# Power.net
KiCad netlist of a schematic drawn in Altium Designer
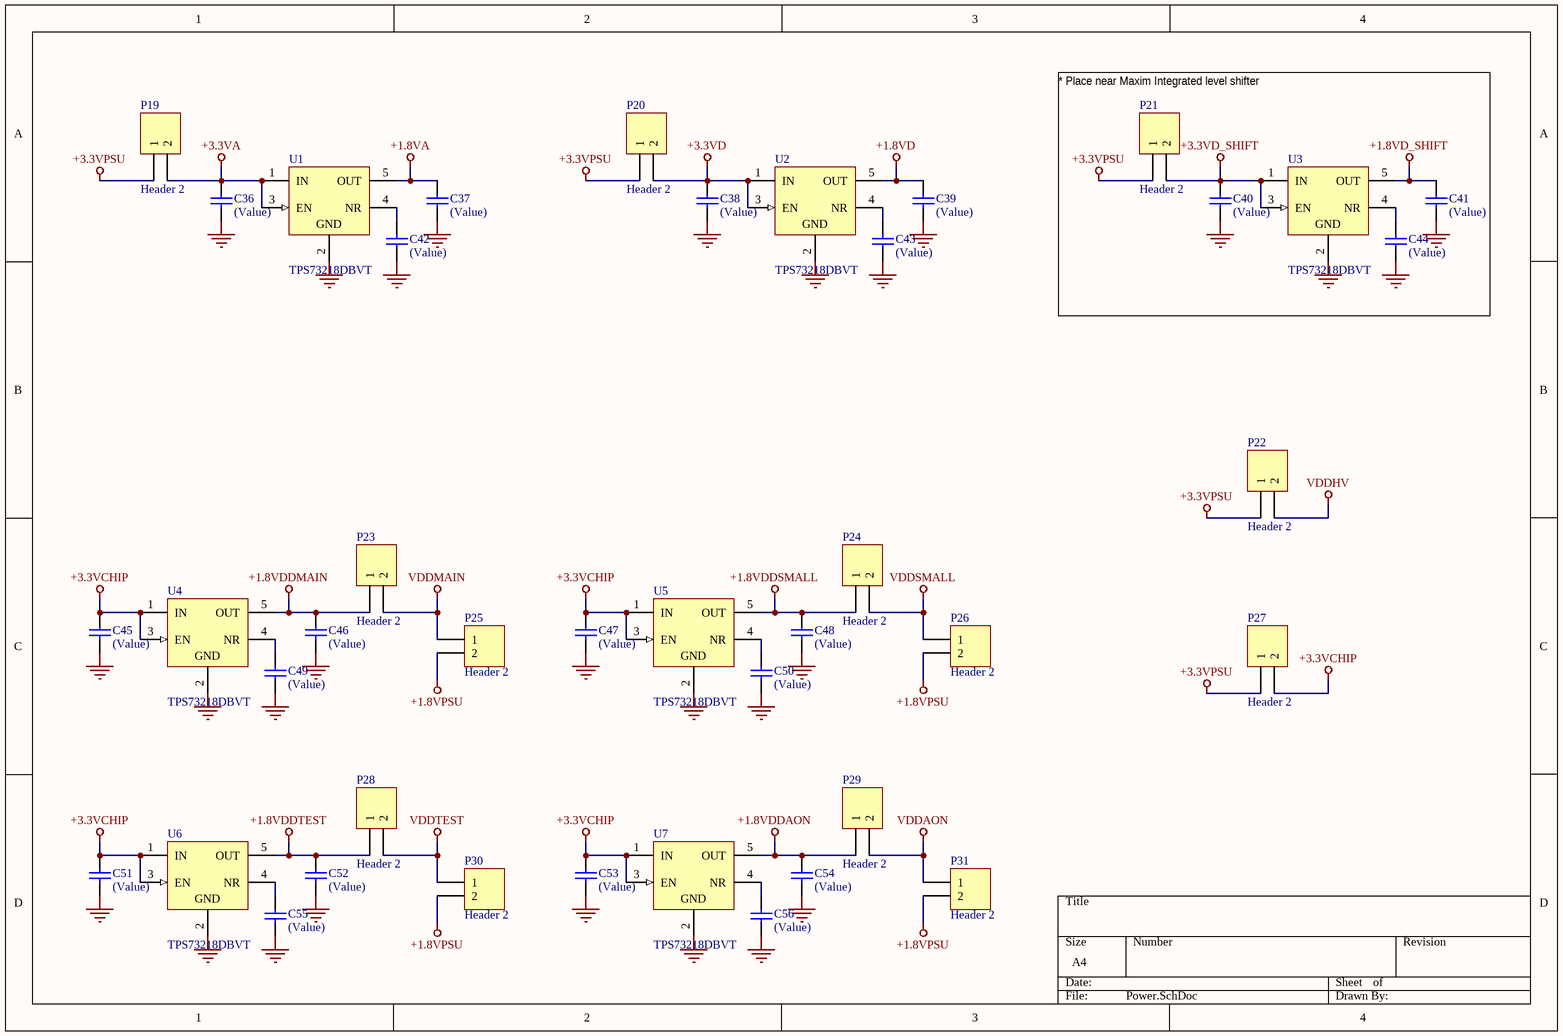
[diagram p0: Power.SchDoc]

(export (version "E")
  (design (tool "Eeschema 10.0.6"))
  (components
    (comp (ref "C36")
      (value "(Value)")
      (footprint "CAPC1608X90X35ML10T15")
      (description "0603")
      (fields (field (name "MANUFACTURER") "Murata"))
      (libsource (lib "Altium Content Vault") (part "CAP-NP-2"))
    )
    (comp (ref "C37")
      (value "(Value)")
      (footprint "CAPC1608X90X35ML10T15")
      (description "0603")
      (fields (field (name "MANUFACTURER") "Murata"))
      (libsource (lib "Altium Content Vault") (part "CAP-NP-2"))
    )
    (comp (ref "C38")
      (value "(Value)")
      (footprint "CAPC1608X90X35ML10T15")
      (description "0603")
      (fields (field (name "MANUFACTURER") "Murata"))
      (libsource (lib "Altium Content Vault") (part "CAP-NP-2"))
    )
    (comp (ref "C39")
      (value "(Value)")
      (footprint "CAPC1608X90X35ML10T15")
      (description "0603")
      (fields (field (name "MANUFACTURER") "Murata"))
      (libsource (lib "Altium Content Vault") (part "CAP-NP-2"))
    )
    (comp (ref "C40")
      (value "(Value)")
      (footprint "CAPC1608X90X35ML10T15")
      (description "0603")
      (fields (field (name "MANUFACTURER") "Murata"))
      (libsource (lib "Altium Content Vault") (part "CAP-NP-2"))
    )
    (comp (ref "C41")
      (value "(Value)")
      (footprint "CAPC1608X90X35ML10T15")
      (description "0603")
      (fields (field (name "MANUFACTURER") "Murata"))
      (libsource (lib "Altium Content Vault") (part "CAP-NP-2"))
    )
    (comp (ref "C42")
      (value "(Value)")
      (footprint "CAPC1608X90X35ML10T15")
      (description "0603")
      (fields (field (name "MANUFACTURER") "Murata"))
      (libsource (lib "Altium Content Vault") (part "CAP-NP-2"))
    )
    (comp (ref "C43")
      (value "(Value)")
      (footprint "CAPC1608X90X35ML10T15")
      (description "0603")
      (fields (field (name "MANUFACTURER") "Murata"))
      (libsource (lib "Altium Content Vault") (part "CAP-NP-2"))
    )
    (comp (ref "C44")
      (value "(Value)")
      (footprint "CAPC1608X90X35ML10T15")
      (description "0603")
      (fields (field (name "MANUFACTURER") "Murata"))
      (libsource (lib "Altium Content Vault") (part "CAP-NP-2"))
    )
    (comp (ref "C45")
      (value "(Value)")
      (footprint "CAPC1608X90X35ML10T15")
      (description "0603")
      (fields (field (name "MANUFACTURER") "Murata"))
      (libsource (lib "Altium Content Vault") (part "CAP-NP-2"))
    )
    (comp (ref "C46")
      (value "(Value)")
      (footprint "CAPC1608X90X35ML10T15")
      (description "0603")
      (fields (field (name "MANUFACTURER") "Murata"))
      (libsource (lib "Altium Content Vault") (part "CAP-NP-2"))
    )
    (comp (ref "C47")
      (value "(Value)")
      (footprint "CAPC1608X90X35ML10T15")
      (description "0603")
      (fields (field (name "MANUFACTURER") "Murata"))
      (libsource (lib "Altium Content Vault") (part "CAP-NP-2"))
    )
    (comp (ref "C48")
      (value "(Value)")
      (footprint "CAPC1608X90X35ML10T15")
      (description "0603")
      (fields (field (name "MANUFACTURER") "Murata"))
      (libsource (lib "Altium Content Vault") (part "CAP-NP-2"))
    )
    (comp (ref "C49")
      (value "(Value)")
      (footprint "CAPC1608X90X35ML10T15")
      (description "0603")
      (fields (field (name "MANUFACTURER") "Murata"))
      (libsource (lib "Altium Content Vault") (part "CAP-NP-2"))
    )
    (comp (ref "C50")
      (value "(Value)")
      (footprint "CAPC1608X90X35ML10T15")
      (description "0603")
      (fields (field (name "MANUFACTURER") "Murata"))
      (libsource (lib "Altium Content Vault") (part "CAP-NP-2"))
    )
    (comp (ref "C51")
      (value "(Value)")
      (footprint "CAPC1608X90X35ML10T15")
      (description "0603")
      (fields (field (name "MANUFACTURER") "Murata"))
      (libsource (lib "Altium Content Vault") (part "CAP-NP-2"))
    )
    (comp (ref "C52")
      (value "(Value)")
      (footprint "CAPC1608X90X35ML10T15")
      (description "0603")
      (fields (field (name "MANUFACTURER") "Murata"))
      (libsource (lib "Altium Content Vault") (part "CAP-NP-2"))
    )
    (comp (ref "C53")
      (value "(Value)")
      (footprint "CAPC1608X90X35ML10T15")
      (description "0603")
      (fields (field (name "MANUFACTURER") "Murata"))
      (libsource (lib "Altium Content Vault") (part "CAP-NP-2"))
    )
    (comp (ref "C54")
      (value "(Value)")
      (footprint "CAPC1608X90X35ML10T15")
      (description "0603")
      (fields (field (name "MANUFACTURER") "Murata"))
      (libsource (lib "Altium Content Vault") (part "CAP-NP-2"))
    )
    (comp (ref "C55")
      (value "(Value)")
      (footprint "CAPC1608X90X35ML10T15")
      (description "0603")
      (fields (field (name "MANUFACTURER") "Murata"))
      (libsource (lib "Altium Content Vault") (part "CAP-NP-2"))
    )
    (comp (ref "C56")
      (value "(Value)")
      (footprint "CAPC1608X90X35ML10T15")
      (description "0603")
      (fields (field (name "MANUFACTURER") "Murata"))
      (libsource (lib "Altium Content Vault") (part "CAP-NP-2"))
    )
    (comp (ref "P19")
      (value "Header 2")
      (footprint "HDR1X2")
      (description "Header, 2-Pin")
      (fields (field (name "PUBLISHER") "Altium Limited"))
      (libsource (lib "Miscellaneous Connectors") (part "Header 2"))
    )
    (comp (ref "P20")
      (value "Header 2")
      (footprint "HDR1X2")
      (description "Header, 2-Pin")
      (fields (field (name "PUBLISHER") "Altium Limited"))
      (libsource (lib "Miscellaneous Connectors") (part "Header 2"))
    )
    (comp (ref "P21")
      (value "Header 2")
      (footprint "HDR1X2")
      (description "Header, 2-Pin")
      (fields (field (name "PUBLISHER") "Altium Limited"))
      (libsource (lib "Miscellaneous Connectors") (part "Header 2"))
    )
    (comp (ref "P22")
      (value "Header 2")
      (footprint "HDR1X2")
      (description "Header, 2-Pin")
      (fields (field (name "PUBLISHER") "Altium Limited"))
      (libsource (lib "Miscellaneous Connectors") (part "Header 2"))
    )
    (comp (ref "P23")
      (value "Header 2")
      (footprint "HDR1X2")
      (description "Header, 2-Pin")
      (fields (field (name "PUBLISHER") "Altium Limited"))
      (libsource (lib "Miscellaneous Connectors") (part "Header 2"))
    )
    (comp (ref "P24")
      (value "Header 2")
      (footprint "HDR1X2")
      (description "Header, 2-Pin")
      (fields (field (name "PUBLISHER") "Altium Limited"))
      (libsource (lib "Miscellaneous Connectors") (part "Header 2"))
    )
    (comp (ref "P25")
      (value "Header 2")
      (footprint "HDR1X2")
      (description "Header, 2-Pin")
      (fields (field (name "PUBLISHER") "Altium Limited"))
      (libsource (lib "") (part "Header 2_1"))
    )
    (comp (ref "P26")
      (value "Header 2")
      (footprint "HDR1X2")
      (description "Header, 2-Pin")
      (fields (field (name "PUBLISHER") "Altium Limited"))
      (libsource (lib "") (part "Header 2_1"))
    )
    (comp (ref "P27")
      (value "Header 2")
      (footprint "HDR1X2")
      (description "Header, 2-Pin")
      (fields (field (name "PUBLISHER") "Altium Limited"))
      (libsource (lib "Miscellaneous Connectors") (part "Header 2"))
    )
    (comp (ref "P28")
      (value "Header 2")
      (footprint "HDR1X2")
      (description "Header, 2-Pin")
      (fields (field (name "PUBLISHER") "Altium Limited"))
      (libsource (lib "Miscellaneous Connectors") (part "Header 2"))
    )
    (comp (ref "P29")
      (value "Header 2")
      (footprint "HDR1X2")
      (description "Header, 2-Pin")
      (fields (field (name "PUBLISHER") "Altium Limited"))
      (libsource (lib "Miscellaneous Connectors") (part "Header 2"))
    )
    (comp (ref "P30")
      (value "Header 2")
      (footprint "HDR1X2")
      (description "Header, 2-Pin")
      (fields (field (name "PUBLISHER") "Altium Limited"))
      (libsource (lib "") (part "Header 2_1"))
    )
    (comp (ref "P31")
      (value "Header 2")
      (footprint "HDR1X2")
      (description "Header, 2-Pin")
      (fields (field (name "PUBLISHER") "Altium Limited"))
      (libsource (lib "") (part "Header 2_1"))
    )
    (comp (ref "U1")
      (value "TPS73218DBVT")
      (footprint "DBV0005A_N")
      (fields (field (name "MANUFACTURER") "Texas Instruments"))
      (libsource (lib "Altium Content Vault") (part "TI-TPS79NXX-YYSOT5"))
    )
    (comp (ref "U2")
      (value "TPS73218DBVT")
      (footprint "DBV0005A_N")
      (fields (field (name "MANUFACTURER") "Texas Instruments"))
      (libsource (lib "Altium Content Vault") (part "TI-TPS79NXX-YYSOT5"))
    )
    (comp (ref "U3")
      (value "TPS73218DBVT")
      (footprint "DBV0005A_N")
      (fields (field (name "MANUFACTURER") "Texas Instruments"))
      (libsource (lib "Altium Content Vault") (part "TI-TPS79NXX-YYSOT5"))
    )
    (comp (ref "U4")
      (value "TPS73218DBVT")
      (footprint "DBV0005A_N")
      (fields (field (name "MANUFACTURER") "Texas Instruments"))
      (libsource (lib "Altium Content Vault") (part "TI-TPS79NXX-YYSOT5"))
    )
    (comp (ref "U5")
      (value "TPS73218DBVT")
      (footprint "DBV0005A_N")
      (fields (field (name "MANUFACTURER") "Texas Instruments"))
      (libsource (lib "Altium Content Vault") (part "TI-TPS79NXX-YYSOT5"))
    )
    (comp (ref "U6")
      (value "TPS73218DBVT")
      (footprint "DBV0005A_N")
      (fields (field (name "MANUFACTURER") "Texas Instruments"))
      (libsource (lib "Altium Content Vault") (part "TI-TPS79NXX-YYSOT5"))
    )
    (comp (ref "U7")
      (value "TPS73218DBVT")
      (footprint "DBV0005A_N")
      (fields (field (name "MANUFACTURER") "Texas Instruments"))
      (libsource (lib "Altium Content Vault") (part "TI-TPS79NXX-YYSOT5"))
    )
  )
  (nets
    (net (code "1") (name "+1.8VA") (class "Default")
      (node (ref "C37") (pin "1") (pinfunction "1_1") (pintype "passive"))
      (node (ref "U1") (pin "5") (pinfunction "OUT_5") (pintype "power_in"))
    )
    (net (code "2") (name "+1.8VD") (class "Default")
      (node (ref "C39") (pin "1") (pinfunction "1_1") (pintype "passive"))
      (node (ref "U2") (pin "5") (pinfunction "OUT_5") (pintype "power_in"))
    )
    (net (code "3") (name "+1.8VDDAON") (class "Default")
      (node (ref "C54") (pin "1") (pinfunction "1_1") (pintype "passive"))
      (node (ref "P29") (pin "1") (pinfunction "1_1") (pintype "passive"))
      (node (ref "U7") (pin "5") (pinfunction "OUT_5") (pintype "power_in"))
    )
    (net (code "4") (name "+1.8VDDMAIN") (class "Default")
      (node (ref "C46") (pin "1") (pinfunction "1_1") (pintype "passive"))
      (node (ref "P23") (pin "1") (pinfunction "1_1") (pintype "passive"))
      (node (ref "U4") (pin "5") (pinfunction "OUT_5") (pintype "power_in"))
    )
    (net (code "5") (name "+1.8VDDSMALL") (class "Default")
      (node (ref "C48") (pin "1") (pinfunction "1_1") (pintype "passive"))
      (node (ref "P24") (pin "1") (pinfunction "1_1") (pintype "passive"))
      (node (ref "U5") (pin "5") (pinfunction "OUT_5") (pintype "power_in"))
    )
    (net (code "6") (name "+1.8VDDTEST") (class "Default")
      (node (ref "C52") (pin "1") (pinfunction "1_1") (pintype "passive"))
      (node (ref "P28") (pin "1") (pinfunction "1_1") (pintype "passive"))
      (node (ref "U6") (pin "5") (pinfunction "OUT_5") (pintype "power_in"))
    )
    (net (code "7") (name "+1.8VD_SHIFT") (class "Default")
      (node (ref "C41") (pin "1") (pinfunction "1_1") (pintype "passive"))
      (node (ref "U3") (pin "5") (pinfunction "OUT_5") (pintype "power_in"))
    )
    (net (code "8") (name "+1.8VPSU") (class "Default")
      (node (ref "P25") (pin "2") (pinfunction "2_2") (pintype "passive"))
      (node (ref "P26") (pin "2") (pinfunction "2_2") (pintype "passive"))
      (node (ref "P30") (pin "2") (pinfunction "2_2") (pintype "passive"))
      (node (ref "P31") (pin "2") (pinfunction "2_2") (pintype "passive"))
    )
    (net (code "9") (name "+3.3VA") (class "Default")
      (node (ref "C36") (pin "1") (pinfunction "1_1") (pintype "passive"))
      (node (ref "P19") (pin "2") (pinfunction "2_2") (pintype "passive"))
      (node (ref "U1") (pin "1") (pinfunction "IN_1") (pintype "power_in"))
      (node (ref "U1") (pin "3") (pinfunction "EN_3") (pintype "input"))
    )
    (net (code "10") (name "+3.3VCHIP") (class "Default")
      (node (ref "C45") (pin "1") (pinfunction "1_1") (pintype "passive"))
      (node (ref "C47") (pin "1") (pinfunction "1_1") (pintype "passive"))
      (node (ref "C51") (pin "1") (pinfunction "1_1") (pintype "passive"))
      (node (ref "C53") (pin "1") (pinfunction "1_1") (pintype "passive"))
      (node (ref "P27") (pin "2") (pinfunction "2_2") (pintype "passive"))
      (node (ref "U4") (pin "1") (pinfunction "IN_1") (pintype "power_in"))
      (node (ref "U4") (pin "3") (pinfunction "EN_3") (pintype "input"))
      (node (ref "U5") (pin "1") (pinfunction "IN_1") (pintype "power_in"))
      (node (ref "U5") (pin "3") (pinfunction "EN_3") (pintype "input"))
      (node (ref "U6") (pin "1") (pinfunction "IN_1") (pintype "power_in"))
      (node (ref "U6") (pin "3") (pinfunction "EN_3") (pintype "input"))
      (node (ref "U7") (pin "1") (pinfunction "IN_1") (pintype "power_in"))
      (node (ref "U7") (pin "3") (pinfunction "EN_3") (pintype "input"))
    )
    (net (code "11") (name "+3.3VD") (class "Default")
      (node (ref "C38") (pin "1") (pinfunction "1_1") (pintype "passive"))
      (node (ref "P20") (pin "2") (pinfunction "2_2") (pintype "passive"))
      (node (ref "U2") (pin "1") (pinfunction "IN_1") (pintype "power_in"))
      (node (ref "U2") (pin "3") (pinfunction "EN_3") (pintype "input"))
    )
    (net (code "12") (name "+3.3VD_SHIFT") (class "Default")
      (node (ref "C40") (pin "1") (pinfunction "1_1") (pintype "passive"))
      (node (ref "P21") (pin "2") (pinfunction "2_2") (pintype "passive"))
      (node (ref "U3") (pin "1") (pinfunction "IN_1") (pintype "power_in"))
      (node (ref "U3") (pin "3") (pinfunction "EN_3") (pintype "input"))
    )
    (net (code "13") (name "+3.3VPSU") (class "Default")
      (node (ref "P19") (pin "1") (pinfunction "1_1") (pintype "passive"))
      (node (ref "P20") (pin "1") (pinfunction "1_1") (pintype "passive"))
      (node (ref "P21") (pin "1") (pinfunction "1_1") (pintype "passive"))
      (node (ref "P22") (pin "1") (pinfunction "1_1") (pintype "passive"))
      (node (ref "P27") (pin "1") (pinfunction "1_1") (pintype "passive"))
    )
    (net (code "14") (name "GND") (class "Default")
      (node (ref "C36") (pin "2") (pinfunction "2_2") (pintype "passive"))
      (node (ref "C37") (pin "2") (pinfunction "2_2") (pintype "passive"))
      (node (ref "C38") (pin "2") (pinfunction "2_2") (pintype "passive"))
      (node (ref "C39") (pin "2") (pinfunction "2_2") (pintype "passive"))
      (node (ref "C40") (pin "2") (pinfunction "2_2") (pintype "passive"))
      (node (ref "C41") (pin "2") (pinfunction "2_2") (pintype "passive"))
      (node (ref "C42") (pin "2") (pinfunction "2_2") (pintype "passive"))
      (node (ref "C43") (pin "2") (pinfunction "2_2") (pintype "passive"))
      (node (ref "C44") (pin "2") (pinfunction "2_2") (pintype "passive"))
      (node (ref "C45") (pin "2") (pinfunction "2_2") (pintype "passive"))
      (node (ref "C46") (pin "2") (pinfunction "2_2") (pintype "passive"))
      (node (ref "C47") (pin "2") (pinfunction "2_2") (pintype "passive"))
      (node (ref "C48") (pin "2") (pinfunction "2_2") (pintype "passive"))
      (node (ref "C49") (pin "2") (pinfunction "2_2") (pintype "passive"))
      (node (ref "C50") (pin "2") (pinfunction "2_2") (pintype "passive"))
      (node (ref "C51") (pin "2") (pinfunction "2_2") (pintype "passive"))
      (node (ref "C52") (pin "2") (pinfunction "2_2") (pintype "passive"))
      (node (ref "C53") (pin "2") (pinfunction "2_2") (pintype "passive"))
      (node (ref "C54") (pin "2") (pinfunction "2_2") (pintype "passive"))
      (node (ref "C55") (pin "2") (pinfunction "2_2") (pintype "passive"))
      (node (ref "C56") (pin "2") (pinfunction "2_2") (pintype "passive"))
      (node (ref "U1") (pin "2") (pinfunction "GND_2") (pintype "power_in"))
      (node (ref "U2") (pin "2") (pinfunction "GND_2") (pintype "power_in"))
      (node (ref "U3") (pin "2") (pinfunction "GND_2") (pintype "power_in"))
      (node (ref "U4") (pin "2") (pinfunction "GND_2") (pintype "power_in"))
      (node (ref "U5") (pin "2") (pinfunction "GND_2") (pintype "power_in"))
      (node (ref "U6") (pin "2") (pinfunction "GND_2") (pintype "power_in"))
      (node (ref "U7") (pin "2") (pinfunction "GND_2") (pintype "power_in"))
    )
    (net (code "15") (name "Net-(U1-NR)") (class "Default")
      (node (ref "C42") (pin "1") (pinfunction "1_1") (pintype "passive"))
      (node (ref "U1") (pin "4") (pinfunction "NR_4") (pintype "passive"))
    )
    (net (code "16") (name "Net-(U2-NR)") (class "Default")
      (node (ref "C43") (pin "1") (pinfunction "1_1") (pintype "passive"))
      (node (ref "U2") (pin "4") (pinfunction "NR_4") (pintype "passive"))
    )
    (net (code "17") (name "Net-(U3-NR)") (class "Default")
      (node (ref "C44") (pin "1") (pinfunction "1_1") (pintype "passive"))
      (node (ref "U3") (pin "4") (pinfunction "NR_4") (pintype "passive"))
    )
    (net (code "18") (name "Net-(U4-NR)") (class "Default")
      (node (ref "C49") (pin "1") (pinfunction "1_1") (pintype "passive"))
      (node (ref "U4") (pin "4") (pinfunction "NR_4") (pintype "passive"))
    )
    (net (code "19") (name "Net-(U5-NR)") (class "Default")
      (node (ref "C50") (pin "1") (pinfunction "1_1") (pintype "passive"))
      (node (ref "U5") (pin "4") (pinfunction "NR_4") (pintype "passive"))
    )
    (net (code "20") (name "Net-(U6-NR)") (class "Default")
      (node (ref "C55") (pin "1") (pinfunction "1_1") (pintype "passive"))
      (node (ref "U6") (pin "4") (pinfunction "NR_4") (pintype "passive"))
    )
    (net (code "21") (name "Net-(U7-NR)") (class "Default")
      (node (ref "C56") (pin "1") (pinfunction "1_1") (pintype "passive"))
      (node (ref "U7") (pin "4") (pinfunction "NR_4") (pintype "passive"))
    )
    (net (code "22") (name "VDDAON") (class "Default")
      (node (ref "P29") (pin "2") (pinfunction "2_2") (pintype "passive"))
      (node (ref "P31") (pin "1") (pinfunction "1_1") (pintype "passive"))
    )
    (net (code "23") (name "VDDHV") (class "Default")
      (node (ref "P22") (pin "2") (pinfunction "2_2") (pintype "passive"))
    )
    (net (code "24") (name "VDDMAIN") (class "Default")
      (node (ref "P23") (pin "2") (pinfunction "2_2") (pintype "passive"))
      (node (ref "P25") (pin "1") (pinfunction "1_1") (pintype "passive"))
    )
    (net (code "25") (name "VDDSMALL") (class "Default")
      (node (ref "P24") (pin "2") (pinfunction "2_2") (pintype "passive"))
      (node (ref "P26") (pin "1") (pinfunction "1_1") (pintype "passive"))
    )
    (net (code "26") (name "VDDTEST") (class "Default")
      (node (ref "P28") (pin "2") (pinfunction "2_2") (pintype "passive"))
      (node (ref "P30") (pin "1") (pinfunction "1_1") (pintype "passive"))
    )
  )
)
